# Power_Stages.net
KiCad netlist of a schematic drawn in Altium Designer
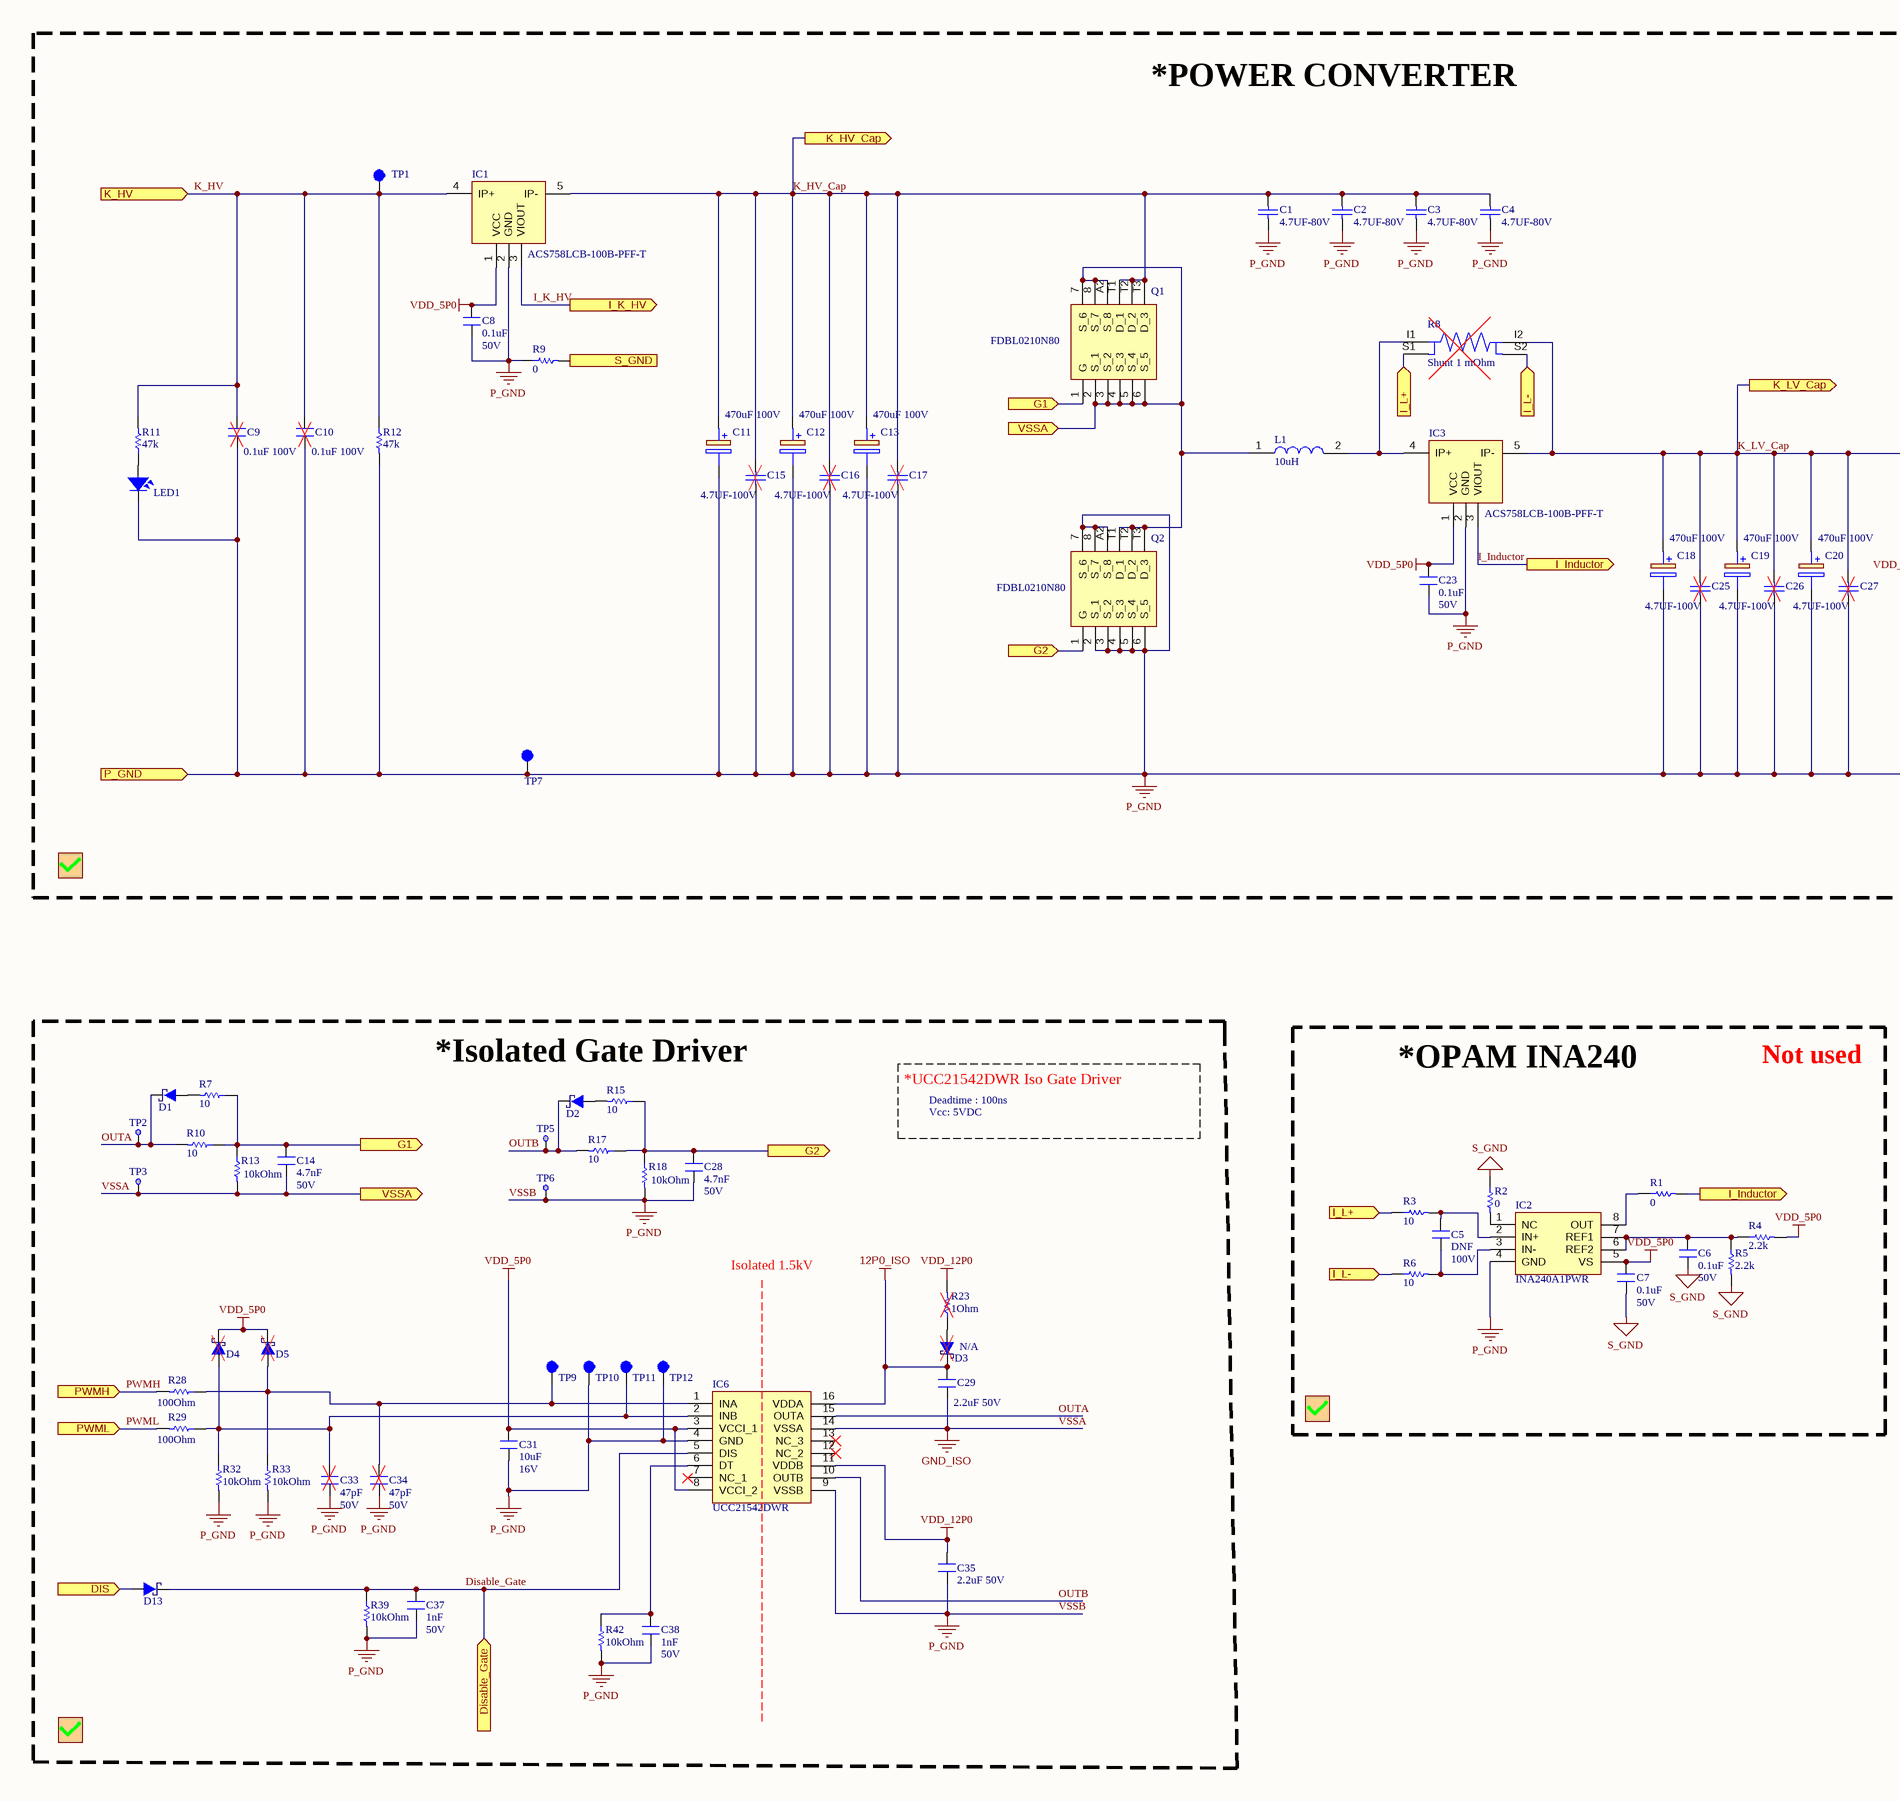
[diagram p0: Power Stages.SchDoc, left]
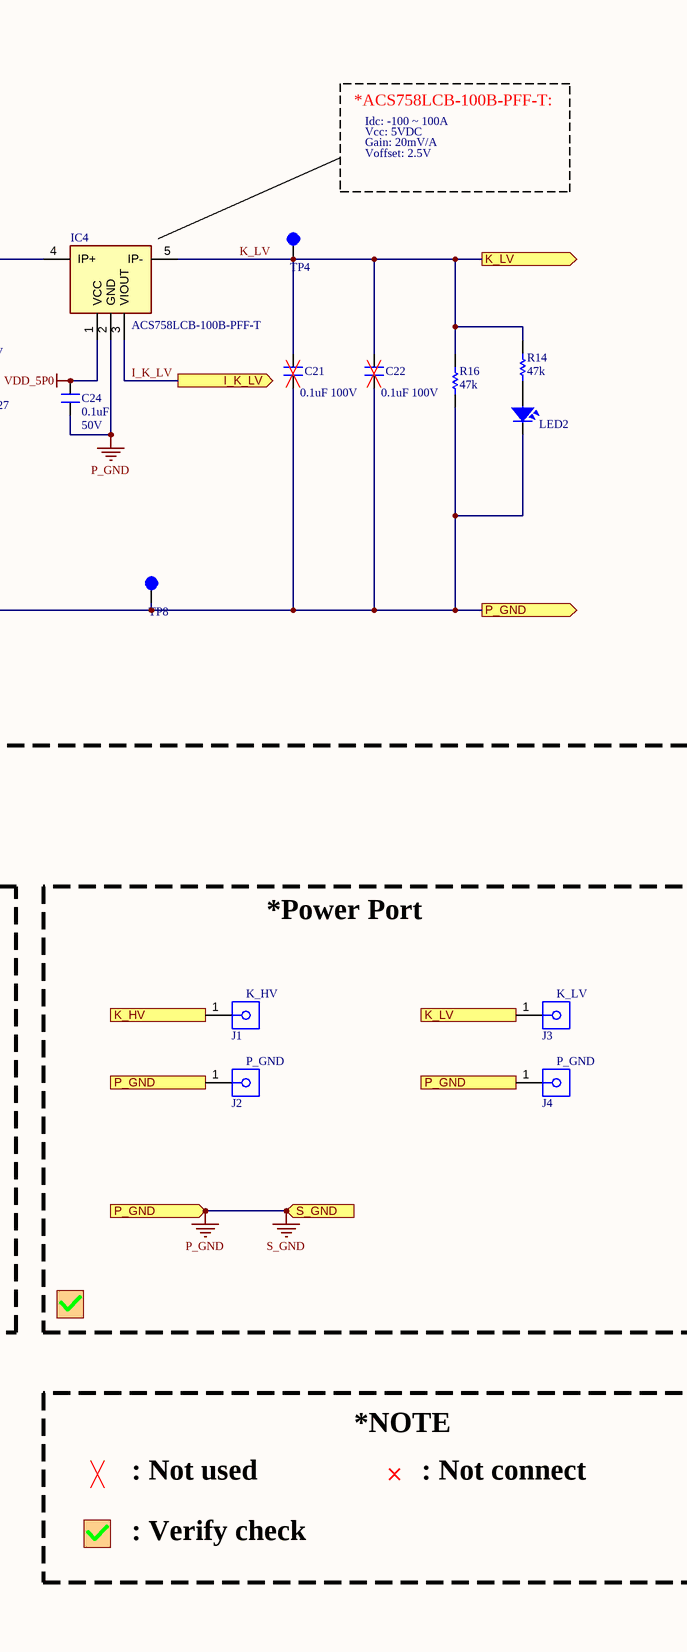
[diagram p1: Power Stages.SchDoc, right]

(export (version "E")
  (design (tool "Eeschema 10.0.6"))
  (components
    (comp (ref "C1")
      (value "4.7UF-80V")
      (footprint "C_1210")
      (description "CAP CER 4.7uF 80V X7R 1210")
      (fields
        (field (name "PART NUMBER") "GRM32ER71K475KE14L")
        (field (name "MANUFACTURER") "TDK Corporation")
      )
      (libsource (lib "DC_DC_Power_V3.0") (part "Cap 1210"))
    )
    (comp (ref "C2")
      (value "4.7UF-80V")
      (footprint "C_1210")
      (description "CAP CER 4.7uF 80V X7R 1210")
      (fields
        (field (name "PART NUMBER") "GRM32ER71K475KE14L")
        (field (name "MANUFACTURER") "TDK Corporation")
      )
      (libsource (lib "DC_DC_Power_V3.0") (part "Cap 1210"))
    )
    (comp (ref "C3")
      (value "4.7UF-80V")
      (footprint "C_1210")
      (description "CAP CER 4.7uF 80V X7R 1210")
      (fields
        (field (name "PART NUMBER") "GRM32ER71K475KE14L")
        (field (name "MANUFACTURER") "TDK Corporation")
      )
      (libsource (lib "DC_DC_Power_V3.0") (part "Cap 1210"))
    )
    (comp (ref "C4")
      (value "4.7UF-80V")
      (footprint "C_1210")
      (description "CAP CER 4.7uF 80V X7R 1210")
      (fields
        (field (name "PART NUMBER") "GRM32ER71K475KE14L")
        (field (name "MANUFACTURER") "TDK Corporation")
      )
      (libsource (lib "DC_DC_Power_V3.0") (part "Cap 1210"))
    )
    (comp (ref "C5")
      (value "DNF")
      (footprint "C_0603")
      (fields
        (field (name "MANUFACTURER") "Murata Electronics")
        (field (name "PART NUMBER") "GCM188R71E102KA37D")
        (field (name "ALTIUM_VALUE") "100V")
      )
      (libsource (lib "S1200_Capacitor") (part "Cap_Cer_0603_1nF"))
    )
    (comp (ref "C6")
      (value "0.1uF")
      (footprint "C_0603")
      (description "CAP CER 0.1UF 50V X7R 0603")
      (fields
        (field (name "MANUFACTURER") "Murata Electronics")
        (field (name "PART NUMBER") "GCM188R71E102KA37D")
        (field (name "ALTIUM_VALUE") "50V")
      )
      (libsource (lib "S1200_Capacitor") (part "Cap_Cer_0603_1nF"))
    )
    (comp (ref "C7")
      (value "0.1uF")
      (footprint "C_0603")
      (description "CAP CER 0.1UF 50V X7R 0603")
      (fields
        (field (name "MANUFACTURER") "Murata Electronics")
        (field (name "PART NUMBER") "GCM188R71E102KA37D")
        (field (name "ALTIUM_VALUE") "50V")
      )
      (libsource (lib "S1200_Capacitor") (part "Cap_Cer_0603_1nF"))
    )
    (comp (ref "C8")
      (value "0.1uF")
      (footprint "C_0603")
      (description "CAP CER 0.1UF 16V X5R 0603")
      (fields
        (field (name "MANUFACTURER") "Murata Electronics")
        (field (name "PART NUMBER") "CL21A106KOCLRNC")
        (field (name "ALTIUM_VALUE") "50V")
      )
      (libsource (lib "S1200_Capacitor") (part "Cap_Cer_0603_1nF_25V"))
    )
    (comp (ref "C9")
      (value "0.1uF 100V")
      (footprint "C_1206")
      (description "Ceramic Capacitor 1206 (+-10% TH)/(+10%SMD)")
      (fields
        (field (name "MANUFACTURER") "TDK Corporation")
        (field (name "PART NUMBER") "C3216X7R2A105K160AA")
      )
      (libsource (lib "S1200_Capacitor") (part "Cap_Cer_1206_1uF"))
    )
    (comp (ref "C10")
      (value "0.1uF 100V")
      (footprint "C_1206")
      (description "Ceramic Capacitor 1206 (+-10% TH)/(+10%SMD)")
      (fields
        (field (name "MANUFACTURER") "TDK Corporation")
        (field (name "PART NUMBER") "C3216X7R2A105K160AA")
      )
      (libsource (lib "S1200_Capacitor") (part "Cap_Cer_1206_1uF"))
    )
    (comp (ref "C11")
      (value "470uF 100V")
      (footprint "CAP-ALU-13MM*30MM")
      (description "CAP ALUM 470UF 20% 80V RADIAL")
      (fields (field (name "PART NUMBER") "EEU-FS1K471L"))
      (libsource (lib "Tienanh") (part "100ZLH470MEFC16X31.5"))
    )
    (comp (ref "C12")
      (value "470uF 100V")
      (footprint "CAP-ALU-13MM*30MM")
      (description "CAP ALUM 470UF 20% 80V RADIAL")
      (fields (field (name "PART NUMBER") "EEU-FS1K471L"))
      (libsource (lib "Tienanh") (part "100ZLH470MEFC16X31.5"))
    )
    (comp (ref "C13")
      (value "470uF 100V")
      (footprint "CAP-ALU-13MM*30MM")
      (description "CAP ALUM 470UF 20% 80V RADIAL")
      (fields (field (name "PART NUMBER") "EEU-FS1K471L"))
      (libsource (lib "Tienanh") (part "100ZLH470MEFC16X31.5"))
    )
    (comp (ref "C14")
      (value "4.7nF")
      (footprint "C_0603")
      (description "CAP CER 0805 4.7NF 50V C0G 5%")
      (fields
        (field (name "MANUFACTURER") "KEMET")
        (field (name "PART NUMBER") "C0805C472J5GECAUTO")
        (field (name "ALTIUM_VALUE") "50V")
      )
      (libsource (lib "S1200_Capacitor") (part "Cap_Cer_0603_1nF_25V"))
    )
    (comp (ref "C15")
      (value "4.7UF-100V")
      (footprint "C_1210")
      (description "CAP CER 4.7uF 80V X7R 1210")
      (fields
        (field (name "PART NUMBER") "GRM32ER71K475KE14L")
        (field (name "MANUFACTURER") "TDK Corporation")
      )
      (libsource (lib "DC_DC_Power_V3.0") (part "Cap 1210"))
    )
    (comp (ref "C16")
      (value "4.7UF-100V")
      (footprint "C_1210")
      (description "CAP CER 4.7uF 80V X7R 1210")
      (fields
        (field (name "PART NUMBER") "GRM32ER71K475KE14L")
        (field (name "MANUFACTURER") "TDK Corporation")
      )
      (libsource (lib "DC_DC_Power_V3.0") (part "Cap 1210"))
    )
    (comp (ref "C17")
      (value "4.7UF-100V")
      (footprint "C_1210")
      (description "CAP CER 4.7uF 80V X7R 1210")
      (fields
        (field (name "PART NUMBER") "GRM32ER71K475KE14L")
        (field (name "MANUFACTURER") "TDK Corporation")
      )
      (libsource (lib "DC_DC_Power_V3.0") (part "Cap 1210"))
    )
    (comp (ref "C18")
      (value "470uF 100V")
      (footprint "CAP-ALU-13MM*30MM")
      (description "CAP ALUM 470UF 20% 80V RADIAL")
      (fields (field (name "PART NUMBER") "EEU-FS1K471L"))
      (libsource (lib "Tienanh") (part "100ZLH470MEFC16X31.5"))
    )
    (comp (ref "C19")
      (value "470uF 100V")
      (footprint "CAP-ALU-13MM*30MM")
      (description "CAP ALUM 470UF 20% 80V RADIAL")
      (fields (field (name "PART NUMBER") "EEU-FS1K471L"))
      (libsource (lib "Tienanh") (part "100ZLH470MEFC16X31.5"))
    )
    (comp (ref "C20")
      (value "470uF 100V")
      (footprint "CAP-ALU-13MM*30MM")
      (description "CAP ALUM 470UF 20% 80V RADIAL")
      (fields (field (name "PART NUMBER") "EEU-FS1K471L"))
      (libsource (lib "Tienanh") (part "100ZLH470MEFC16X31.5"))
    )
    (comp (ref "C21")
      (value "0.1uF 100V")
      (footprint "C_1206")
      (description "Ceramic Capacitor 1206 (+-10% TH)/(+10%SMD)")
      (fields
        (field (name "MANUFACTURER") "TDK Corporation")
        (field (name "PART NUMBER") "C3216X7R2A105K160AA")
      )
      (libsource (lib "S1200_Capacitor") (part "Cap_Cer_1206_1uF"))
    )
    (comp (ref "C22")
      (value "0.1uF 100V")
      (footprint "C_1206")
      (description "Ceramic Capacitor 1206 (+-10% TH)/(+10%SMD)")
      (fields
        (field (name "MANUFACTURER") "TDK Corporation")
        (field (name "PART NUMBER") "C3216X7R2A105K160AA")
      )
      (libsource (lib "S1200_Capacitor") (part "Cap_Cer_1206_1uF"))
    )
    (comp (ref "C23")
      (value "0.1uF")
      (footprint "C_0603")
      (description "CAP CER 0.1UF 16V X5R 0603")
      (fields
        (field (name "MANUFACTURER") "Murata Electronics")
        (field (name "PART NUMBER") "CL21A106KOCLRNC")
        (field (name "ALTIUM_VALUE") "50V")
      )
      (libsource (lib "S1200_Capacitor") (part "Cap_Cer_0603_1nF_25V"))
    )
    (comp (ref "C24")
      (value "0.1uF")
      (footprint "C_0603")
      (description "CAP CER 0.1UF 16V X5R 0603")
      (fields
        (field (name "MANUFACTURER") "Murata Electronics")
        (field (name "PART NUMBER") "CL21A106KOCLRNC")
        (field (name "ALTIUM_VALUE") "50V")
      )
      (libsource (lib "S1200_Capacitor") (part "Cap_Cer_0603_1nF_25V"))
    )
    (comp (ref "C25")
      (value "4.7UF-100V")
      (footprint "C_1210")
      (description "CAP CER 4.7uF 80V X7R 1210")
      (fields
        (field (name "PART NUMBER") "GRM32ER71K475KE14L")
        (field (name "MANUFACTURER") "TDK Corporation")
      )
      (libsource (lib "DC_DC_Power_V3.0") (part "Cap 1210"))
    )
    (comp (ref "C26")
      (value "4.7UF-100V")
      (footprint "C_1210")
      (description "CAP CER 4.7uF 80V X7R 1210")
      (fields
        (field (name "PART NUMBER") "GRM32ER71K475KE14L")
        (field (name "MANUFACTURER") "TDK Corporation")
      )
      (libsource (lib "DC_DC_Power_V3.0") (part "Cap 1210"))
    )
    (comp (ref "C27")
      (value "4.7UF-100V")
      (footprint "C_1210")
      (description "CAP CER 4.7uF 80V X7R 1210")
      (fields
        (field (name "PART NUMBER") "GRM32ER71K475KE14L")
        (field (name "MANUFACTURER") "TDK Corporation")
      )
      (libsource (lib "DC_DC_Power_V3.0") (part "Cap 1210"))
    )
    (comp (ref "C28")
      (value "4.7nF")
      (footprint "C_0603")
      (description "CAP CER 0805 4.7NF 50V C0G 5%")
      (fields
        (field (name "MANUFACTURER") "KEMET")
        (field (name "PART NUMBER") "C0805C472J5GECAUTO")
        (field (name "ALTIUM_VALUE") "50V")
      )
      (libsource (lib "S1200_Capacitor") (part "Cap_Cer_0603_1nF_25V"))
    )
    (comp (ref "C29")
      (value "2.2uF 50V")
      (footprint "C_1206")
      (description "Ceramic Capacitor 1206 (+-10% TH)/(+10%SMD)")
      (fields
        (field (name "MANUFACTURER") "TDK Corporation")
        (field (name "PART NUMBER") "C3216X7R2A105K160AA")
      )
      (libsource (lib "S1200_Capacitor") (part "Cap_Cer_1206_1uF"))
    )
    (comp (ref "C31")
      (value "10uF")
      (footprint "C_0805")
      (description "CAP CER 10uF 16V X7R 0805")
      (fields
        (field (name "MANUFACTURER") "Kemet")
        (field (name "PART NUMBER") "CL21A106KOCLRNC")
        (field (name "ALTIUM_VALUE") "16V")
      )
      (libsource (lib "S1200_Capacitor") (part "Cap_Cer_0805_10pF"))
    )
    (comp (ref "C33")
      (value "47pF")
      (footprint "C_0603")
      (description "CAP CER 1nF 50V X7R 0603")
      (fields
        (field (name "MANUFACTURER") "Murata Electronics")
        (field (name "PART NUMBER") "GCM188R71E102KA37D")
        (field (name "ALTIUM_VALUE") "50V")
      )
      (libsource (lib "S1200_Capacitor") (part "Cap_Cer_0603_1nF_25V"))
    )
    (comp (ref "C34")
      (value "47pF")
      (footprint "C_0603")
      (description "CAP CER 1nF 50V X7R 0603")
      (fields
        (field (name "MANUFACTURER") "Murata Electronics")
        (field (name "PART NUMBER") "GCM188R71E102KA37D")
        (field (name "ALTIUM_VALUE") "50V")
      )
      (libsource (lib "S1200_Capacitor") (part "Cap_Cer_0603_1nF_25V"))
    )
    (comp (ref "C35")
      (value "2.2uF 50V")
      (footprint "C_1206")
      (description "Ceramic Capacitor 1206 (+-10% TH)/(+10%SMD)")
      (fields
        (field (name "MANUFACTURER") "TDK Corporation")
        (field (name "PART NUMBER") "C3216X7R2A105K160AA")
      )
      (libsource (lib "S1200_Capacitor") (part "Cap_Cer_1206_1uF"))
    )
    (comp (ref "C37")
      (value "1nF")
      (footprint "C_0603")
      (description "CAP CER 1nF 50V X7R 0603")
      (fields
        (field (name "MANUFACTURER") "Murata Electronics")
        (field (name "PART NUMBER") "GCM188R71E102KA37D")
        (field (name "ALTIUM_VALUE") "50V")
      )
      (libsource (lib "S1200_Capacitor") (part "Cap_Cer_0603_1nF_25V"))
    )
    (comp (ref "C38")
      (value "1nF")
      (footprint "C_0603")
      (description "CAP CER 1nF 50V X7R 0603")
      (fields
        (field (name "MANUFACTURER") "Murata Electronics")
        (field (name "PART NUMBER") "GCM188R71E102KA37D")
        (field (name "ALTIUM_VALUE") "50V")
      )
      (libsource (lib "S1200_Capacitor") (part "Cap_Cer_0603_1nF_25V"))
    )
    (comp (ref "D1")
      (value "B0520WS-7-F")
      (footprint "SOD323F")
      (description "DIODE SCHOTTKY 20V 1A SOD323F")
      (fields
        (field (name "MANUFACTURER") "Nexperia USA Inc.")
        (field (name "PART NUMBER") "PMEG2010AEJ,115")
      )
      (libsource (lib "Motor Control SELEX MOTORS JSC") (part "PMEG2010AEJ,115"))
    )
    (comp (ref "D2")
      (value "B0520WS-7-F")
      (footprint "SOD323F")
      (description "DIODE SCHOTTKY 20V 1A SOD323F")
      (fields
        (field (name "MANUFACTURER") "Nexperia USA Inc.")
        (field (name "PART NUMBER") "PMEG2010AEJ,115")
      )
      (libsource (lib "Motor Control SELEX MOTORS JSC") (part "PMEG2010AEJ,115"))
    )
    (comp (ref "D3")
      (value "PMEG2010AEJ,115")
      (footprint "SOD123")
      (description "DIODE SCHOTTKY 20V 1A SOD323F")
      (fields (field (name "MANUFACTURER") "Nexperia USA Inc.") (field (name "VOLTAGE") "20 V"))
      (libsource (lib "Motor Control SELEX MOTORS JSC") (part "PMEG2010AEJ,115"))
    )
    (comp (ref "D4")
      (value "PMEG2010AEJ,115")
      (footprint "SOD323F")
      (description "DIODE SCHOTTKY 30V 0.2A SOD323F")
      (fields (field (name "MANUFACTURER") "Nexperia USA Inc.") (field (name "PART NUMBER") "BAT54HT1G"))
      (libsource (lib "Motor Control SELEX MOTORS JSC") (part "PMEG2010AEJ,115"))
    )
    (comp (ref "D5")
      (value "PMEG2010AEJ,115")
      (footprint "SOD323F")
      (description "DIODE SCHOTTKY 30V 0.2A SOD323F")
      (fields (field (name "MANUFACTURER") "Nexperia USA Inc.") (field (name "PART NUMBER") "BAT54HT1G"))
      (libsource (lib "Motor Control SELEX MOTORS JSC") (part "PMEG2010AEJ,115"))
    )
    (comp (ref "D13")
      (value "PMEG2010AEJ,115")
      (footprint "SOD323F")
      (description "DIODE SCHOTTKY 20V 1A SOD323F")
      (fields (field (name "MANUFACTURER") "Nexperia USA Inc.") (field (name "VOLTAGE") "20 V"))
      (libsource (lib "Motor Control SELEX MOTORS JSC") (part "PMEG2010AEJ,115"))
    )
    (comp (ref "IC1")
      (value "ACS758LCB-100B-PFF-T")
      (footprint "ACS772ECB200BPFFT")
      (description "Integrated Circuit")
      (fields (field (name "MOUSER PART NUMBER") "250-758LCB100BPFFT"))
      (libsource (lib "Tienanh") (part "ACS758LCB-100B-PFF-T"))
    )
    (comp (ref "IC2")
      (value "INA240A1PWR")
      (footprint "SOP65P640X120-8N")
      (description "Integrated Circuit")
      (fields (field (name "MOUSER PART NUMBER") "595-INA240A1PWR"))
      (libsource (lib "*") (part "INA240A1PWR"))
    )
    (comp (ref "IC3")
      (value "ACS758LCB-100B-PFF-T")
      (footprint "ACS772ECB200BPFFT")
      (description "Integrated Circuit")
      (fields (field (name "MOUSER PART NUMBER") "250-758LCB100BPFFT"))
      (libsource (lib "Tienanh") (part "ACS758LCB-100B-PFF-T"))
    )
    (comp (ref "IC4")
      (value "ACS758LCB-100B-PFF-T")
      (footprint "ACS772ECB200BPFFT")
      (description "Integrated Circuit")
      (fields (field (name "MOUSER PART NUMBER") "250-758LCB100BPFFT"))
      (libsource (lib "Tienanh") (part "ACS758LCB-100B-PFF-T"))
    )
    (comp (ref "IC6")
      (value "UCC21542DWR")
      (footprint "SamacSys:SOIC127P1030X265-16N")
      (description "REINFORCED ISOLATION DUAL-CHANNE")
      (fields (field (name "MOUSER PART NUMBER") "595-UCC21542DWR"))
      (libsource (lib "*") (part "UCC21542DWR"))
    )
    (comp (ref "J1")
      (value "K_HV")
      (footprint "HOLE_5mm_RED")
      (description "Electric Pole 1")
      (libsource (lib "Motor Control SELEX MOTORS JSC") (part "CONN_1P"))
    )
    (comp (ref "J2")
      (value "P_GND")
      (footprint "HOLE_5mm_BLACK")
      (description "Electric Pole 1")
      (libsource (lib "Motor Control SELEX MOTORS JSC") (part "CONN_1P"))
    )
    (comp (ref "J3")
      (value "K_LV")
      (footprint "HOLE_5mm_RED")
      (description "Electric Pole 1")
      (libsource (lib "Motor Control SELEX MOTORS JSC") (part "CONN_1P"))
    )
    (comp (ref "J4")
      (value "P_GND")
      (footprint "HOLE_5mm_BLACK")
      (description "Electric Pole 1")
      (libsource (lib "Motor Control SELEX MOTORS JSC") (part "CONN_1P"))
    )
    (comp (ref "L1")
      (value "10uH")
      (footprint "CSCF3218-6R8MC")
      (description "10-µH with a specified saturation current of 70-A DC")
      (libsource (lib "Sync_Buck1") (part "IHDF1300AEEH4R7K10"))
    )
    (comp (ref "LED1")
      (value "LED SMD")
      (footprint "SM-LED-0805-Blue")
      (description "LED BLUE 1/4W 0805")
      (libsource (lib "syhaunguyen") (part "LED-SMD-0805"))
    )
    (comp (ref "LED2")
      (value "LED SMD")
      (footprint "SM-LED-0805-Blue")
      (description "LED BLUE 1/4W 0805")
      (libsource (lib "syhaunguyen") (part "LED-SMD-0805"))
    )
    (comp (ref "Q1")
      (value "FDBL0210N80")
      (footprint "NTBLS1D5N10MC - duplicate")
      (description "MOSFET N-CH 80V 240A 8HPSOF")
      (fields (field (name "ARROW PART NUMBER") "IPLU300N04S4R8XTMA1"))
      (libsource (lib "*") (part "IPLU300N04S4R8XTMA1"))
    )
    (comp (ref "Q2")
      (value "FDBL0210N80")
      (footprint "NTBLS1D5N10MC - duplicate")
      (description "MOSFET N-CH 80V 240A 8HPSOF")
      (fields (field (name "ARROW PART NUMBER") "IPLU300N04S4R8XTMA1"))
      (libsource (lib "*") (part "IPLU300N04S4R8XTMA1"))
    )
    (comp (ref "R1")
      (value "0")
      (footprint "R_0603")
      (description "RES 0 OHM 1% 1/8W 0603")
      (fields
        (field (name "MANUFACTURER") "KOA Speer Electronics, Inc.")
        (field (name "PART NUMBER") "RK73H1JRTTD10R0F")
      )
      (libsource (lib "S1100_Resistor_FerriteBead") (part "Resistor_0603_10Ohm 1%"))
    )
    (comp (ref "R2")
      (value "0")
      (footprint "R_0603")
      (description "RES 0 OHM 1% 1/8W 0603")
      (fields
        (field (name "MANUFACTURER") "KOA Speer Electronics, Inc.")
        (field (name "PART NUMBER") "RK73H1JRTTD10R0F")
      )
      (libsource (lib "S1100_Resistor_FerriteBead") (part "Resistor_0603_10Ohm 1%"))
    )
    (comp (ref "R3")
      (value "10")
      (footprint "R_0603")
      (description "RES 10 OHM 1% 1/8W 0603")
      (fields
        (field (name "MANUFACTURER") "KOA Speer Electronics, Inc.")
        (field (name "PART NUMBER") "RK73H1JRTTD10R0F")
      )
      (libsource (lib "S1100_Resistor_FerriteBead") (part "Resistor_0603_10Ohm 1%"))
    )
    (comp (ref "R4")
      (value "2.2k")
      (footprint "R_0603")
      (description "RES 2.2k OHM 1% 1/8W 0603")
      (fields
        (field (name "MANUFACTURER") "KOA Speer Electronics, Inc.")
        (field (name "PART NUMBER") "RK73H1JRTTD10R0F")
      )
      (libsource (lib "S1100_Resistor_FerriteBead") (part "Resistor_0603_10Ohm 1%"))
    )
    (comp (ref "R5")
      (value "2.2k")
      (footprint "R_0603")
      (description "RES 2.2k OHM 1% 1/8W 0603")
      (fields
        (field (name "MANUFACTURER") "KOA Speer Electronics, Inc.")
        (field (name "PART NUMBER") "RK73H1JRTTD10R0F")
      )
      (libsource (lib "S1100_Resistor_FerriteBead") (part "Resistor_0603_10Ohm 1%"))
    )
    (comp (ref "R6")
      (value "10")
      (footprint "R_0603")
      (description "RES 10 OHM 1% 1/8W 0603")
      (fields
        (field (name "MANUFACTURER") "KOA Speer Electronics, Inc.")
        (field (name "PART NUMBER") "RK73H1JRTTD10R0F")
      )
      (libsource (lib "S1100_Resistor_FerriteBead") (part "Resistor_0603_10Ohm 1%"))
    )
    (comp (ref "R7")
      (value "10")
      (footprint "R_0805")
      (description "RES 10 OHM 1% 1/8W 0805")
      (fields (field (name "PART NUMBER") "RE0805FRE0710RL") (field (name "MANUFACTURER") "YAGEO"))
      (libsource (lib "S1100_Resistor_FerriteBead") (part "Resistor_0805_10Ohm"))
    )
    (comp (ref "R8")
      (value "Shunt 1 mOhm")
      (footprint "PSG4/PSF4")
      (description "RES 1m OHM 1% 10W NONSTANDARD")
      (fields
        (field (name "MANUFACTURER") "KOA Speer Electronics, Inc.")
        (field (name "PART NUMBER") "PSG4NTEBL500F")
      )
      (libsource (lib "Motor Control SELEX MOTORS JSC") (part "PSG4NTEBL500F"))
    )
    (comp (ref "R9")
      (value "0")
      (footprint "R_0603")
      (description "RES 0 OHM 1% 1/10W 0603")
      (fields (field (name "MANUFACTURER") "YAGEO") (field (name "PART NUMBER") "RC0603FR-7W10KL"))
      (libsource (lib "S1100_Resistor_FerriteBead") (part "Resistor_0603_10kOhm 1%"))
    )
    (comp (ref "R10")
      (value "10")
      (footprint "R_0805")
      (description "RES 10 OHM 1% 1/8W 0805")
      (fields (field (name "PART NUMBER") "RE0805FRE0710RL") (field (name "MANUFACTURER") "YAGEO"))
      (libsource (lib "S1100_Resistor_FerriteBead") (part "Resistor_0805_10Ohm"))
    )
    (comp (ref "R11")
      (value "47k")
      (footprint "R_0603")
      (description "RES 47K OHM 1% 1/10W 0603")
      (fields (field (name "MANUFACTURER") "YAGEO") (field (name "PART NUMBER") "RC0603FR-07100KL"))
      (libsource (lib "S1100_Resistor_FerriteBead") (part "Resistor_0603_10Ohm 1%"))
    )
    (comp (ref "R12")
      (value "47k")
      (footprint "R_1206")
      (description "RES 47K OHM 1/4W 1206")
      (fields (field (name "MANUFACTURER") "YAGEO") (field (name "PART NUMBER") "RC1206JR-070RL"))
      (libsource (lib "S1100_Resistor_FerriteBead") (part "Resistor_1206_0Ohm"))
    )
    (comp (ref "R13")
      (value "10kOhm")
      (footprint "R_0603")
      (description "RES 10K OHM 1% 1/10W 0603")
      (fields (field (name "MANUFACTURER") "YAGEO") (field (name "PART NUMBER") "RC0603FR-7W10KL"))
      (libsource (lib "S1100_Resistor_FerriteBead") (part "Resistor_0603_10kOhm 1%"))
    )
    (comp (ref "R14")
      (value "47k")
      (footprint "R_0603")
      (description "RES 47K OHM 1% 1/10W 0603")
      (fields (field (name "MANUFACTURER") "YAGEO") (field (name "PART NUMBER") "RC0603FR-07100KL"))
      (libsource (lib "S1100_Resistor_FerriteBead") (part "Resistor_0603_10Ohm 1%"))
    )
    (comp (ref "R15")
      (value "10")
      (footprint "R_0805")
      (description "RES 10 OHM 1% 1/8W 0805")
      (fields (field (name "PART NUMBER") "RE0805FRE0710RL") (field (name "MANUFACTURER") "YAGEO"))
      (libsource (lib "S1100_Resistor_FerriteBead") (part "Resistor_0805_10Ohm"))
    )
    (comp (ref "R16")
      (value "47k")
      (footprint "R_1206")
      (description "RES 47K OHM 1/4W 1206")
      (fields (field (name "MANUFACTURER") "YAGEO") (field (name "PART NUMBER") "RC1206JR-070RL"))
      (libsource (lib "S1100_Resistor_FerriteBead") (part "Resistor_1206_0Ohm"))
    )
    (comp (ref "R17")
      (value "10")
      (footprint "R_0805")
      (description "RES 10 OHM 1% 1/8W 0805")
      (fields (field (name "PART NUMBER") "RE0805FRE0710RL") (field (name "MANUFACTURER") "YAGEO"))
      (libsource (lib "S1100_Resistor_FerriteBead") (part "Resistor_0805_10Ohm"))
    )
    (comp (ref "R18")
      (value "10kOhm")
      (footprint "R_0603")
      (description "RES 10K OHM 1% 1/10W 0603")
      (fields (field (name "MANUFACTURER") "YAGEO") (field (name "PART NUMBER") "RC0603FR-7W10KL"))
      (libsource (lib "S1100_Resistor_FerriteBead") (part "Resistor_0603_10kOhm 1%"))
    )
    (comp (ref "R23")
      (value "1Ohm")
      (footprint "R_0603")
      (description "RES 1OHM 1% 1/8W 0603")
      (fields (field (name "MANUFACTURER") "Vishay Dale") (field (name "PART NUMBER") "MCT06030C1008FP500"))
      (libsource (lib "S1100_Resistor_FerriteBead") (part "Resistor_0603_1Ohm"))
    )
    (comp (ref "R28")
      (value "100Ohm")
      (footprint "R_0603")
      (description "RES 100 OHM 1% 1/8W 0603")
      (fields
        (field (name "MANUFACTURER") "KOA Speer Electronics, Inc.")
        (field (name "PART NUMBER") "RK73H1JRTTD1000F")
      )
      (libsource (lib "S1100_Resistor_FerriteBead") (part "Resistor_0603_100Ohm"))
    )
    (comp (ref "R29")
      (value "100Ohm")
      (footprint "R_0603")
      (description "RES 100 OHM 1% 1/8W 0603")
      (fields
        (field (name "MANUFACTURER") "KOA Speer Electronics, Inc.")
        (field (name "PART NUMBER") "RK73H1JRTTD1000F")
      )
      (libsource (lib "S1100_Resistor_FerriteBead") (part "Resistor_0603_100Ohm"))
    )
    (comp (ref "R32")
      (value "10kOhm")
      (footprint "R_0603")
      (description "RES 10 kOHM 1% 1/8W 0603")
      (fields
        (field (name "MANUFACTURER") "KOA Speer Electronics, Inc.")
        (field (name "PART NUMBER") "RK73H1JRTTD1000F")
      )
      (libsource (lib "S1100_Resistor_FerriteBead") (part "Resistor_0603_100Ohm"))
    )
    (comp (ref "R33")
      (value "10kOhm")
      (footprint "R_0603")
      (description "RES 10 kOHM 1% 1/8W 0603")
      (fields
        (field (name "MANUFACTURER") "KOA Speer Electronics, Inc.")
        (field (name "PART NUMBER") "RK73H1JRTTD1000F")
      )
      (libsource (lib "S1100_Resistor_FerriteBead") (part "Resistor_0603_100Ohm"))
    )
    (comp (ref "R39")
      (value "10kOhm")
      (footprint "R_0603")
      (description "RES 10 kOHM 1% 1/8W 0603")
      (fields
        (field (name "MANUFACTURER") "KOA Speer Electronics, Inc.")
        (field (name "PART NUMBER") "RK73H1JRTTD1000F")
      )
      (libsource (lib "S1100_Resistor_FerriteBead") (part "Resistor_0603_100Ohm"))
    )
    (comp (ref "R42")
      (value "10kOhm")
      (footprint "R_0603")
      (description "RES 10 kOHM 1% 1/8W 0603")
      (fields
        (field (name "MANUFACTURER") "KOA Speer Electronics, Inc.")
        (field (name "PART NUMBER") "RK73H1JRTTD1000F")
      )
      (libsource (lib "S1100_Resistor_FerriteBead") (part "Resistor_0603_100Ohm"))
    )
    (comp (ref "TP1")
      (value "Test Point")
      (footprint "TP_1mm_through_hole")
      (description "PC TEST POINT COMPACT RED")
      (fields (field (name "PART NUMBER") "5005") (field (name "MANUFACTURER") "Keystone Electronics"))
      (libsource (lib "Tienanh") (part "Test Point"))
    )
    (comp (ref "TP2")
      (value "TP")
      (footprint "TP_1mm")
      (description "Test Point")
      (fields (field (name "CREATOR") "SELEX MOTORS JSC"))
      (libsource (lib "S1400_Test_Point") (part "Test_Point_1mm"))
    )
    (comp (ref "TP3")
      (value "TP")
      (footprint "TP_1mm")
      (description "Test Point")
      (fields (field (name "CREATOR") "SELEX MOTORS JSC"))
      (libsource (lib "S1400_Test_Point") (part "Test_Point_1mm"))
    )
    (comp (ref "TP4")
      (value "Test Point")
      (footprint "TP_1mm_through_hole")
      (description "PC TEST POINT COMPACT RED")
      (fields (field (name "PART NUMBER") "5005") (field (name "MANUFACTURER") "Keystone Electronics"))
      (libsource (lib "Tienanh") (part "Test Point"))
    )
    (comp (ref "TP5")
      (value "TP")
      (footprint "TP_1mm")
      (description "Test Point")
      (fields (field (name "CREATOR") "SELEX MOTORS JSC"))
      (libsource (lib "S1400_Test_Point") (part "Test_Point_1mm"))
    )
    (comp (ref "TP6")
      (value "TP")
      (footprint "TP_1mm")
      (description "Test Point")
      (fields (field (name "CREATOR") "SELEX MOTORS JSC"))
      (libsource (lib "S1400_Test_Point") (part "Test_Point_1mm"))
    )
    (comp (ref "TP7")
      (value "Test Point")
      (footprint "TP_1mm_through_hole")
      (description "PC TEST POINT COMPACT RED")
      (fields (field (name "PART NUMBER") "5005") (field (name "MANUFACTURER") "Keystone Electronics"))
      (libsource (lib "Tienanh") (part "Test Point"))
    )
    (comp (ref "TP8")
      (value "Test Point")
      (footprint "TP_1mm_through_hole")
      (description "PC TEST POINT COMPACT RED")
      (fields (field (name "PART NUMBER") "5005") (field (name "MANUFACTURER") "Keystone Electronics"))
      (libsource (lib "Tienanh") (part "Test Point"))
    )
    (comp (ref "TP9")
      (value "Test Point")
      (footprint "TP_1mm_through_hole")
      (description "PC TEST POINT COMPACT RED")
      (fields (field (name "PART NUMBER") "5005") (field (name "MANUFACTURER") "Keystone Electronics"))
      (libsource (lib "Tienanh") (part "Test Point"))
    )
    (comp (ref "TP10")
      (value "Test Point")
      (footprint "TP_1mm_through_hole")
      (description "PC TEST POINT COMPACT RED")
      (fields (field (name "PART NUMBER") "5005") (field (name "MANUFACTURER") "Keystone Electronics"))
      (libsource (lib "Tienanh") (part "Test Point"))
    )
    (comp (ref "TP11")
      (value "Test Point")
      (footprint "TP_1mm_through_hole")
      (description "PC TEST POINT COMPACT RED")
      (fields (field (name "PART NUMBER") "5005") (field (name "MANUFACTURER") "Keystone Electronics"))
      (libsource (lib "Tienanh") (part "Test Point"))
    )
    (comp (ref "TP12")
      (value "Test Point")
      (footprint "TP_1mm_through_hole")
      (description "PC TEST POINT COMPACT RED")
      (fields (field (name "PART NUMBER") "5005") (field (name "MANUFACTURER") "Keystone Electronics"))
      (libsource (lib "Tienanh") (part "Test Point"))
    )
  )
  (nets
    (net (code "1") (name "/DIS") (class "Default")
      (node (ref "D13") (pin "1") (pinfunction "1_1") (pintype "passive"))
    )
    (net (code "2") (name "/Disable_Gate") (class "Default")
      (node (ref "C37") (pin "2") (pinfunction "2_2") (pintype "passive"))
      (node (ref "D13") (pin "2") (pinfunction "2_2") (pintype "passive"))
      (node (ref "IC6") (pin "5") (pinfunction "DIS_5") (pintype "passive"))
      (node (ref "R39") (pin "2") (pinfunction "2_2") (pintype "passive"))
    )
    (net (code "3") (name "/G1") (class "Default")
      (node (ref "C14") (pin "2") (pinfunction "2_2") (pintype "passive"))
      (node (ref "Q1") (pin "1") (pinfunction "G_1") (pintype "passive"))
      (node (ref "R10") (pin "2") (pinfunction "2_2") (pintype "passive"))
      (node (ref "R13") (pin "2") (pinfunction "2_2") (pintype "passive"))
      (node (ref "R7") (pin "2") (pinfunction "2_2") (pintype "passive"))
    )
    (net (code "4") (name "/G2") (class "Default")
      (node (ref "C28") (pin "2") (pinfunction "2_2") (pintype "passive"))
      (node (ref "Q2") (pin "1") (pinfunction "G_1") (pintype "passive"))
      (node (ref "R15") (pin "2") (pinfunction "2_2") (pintype "passive"))
      (node (ref "R17") (pin "2") (pinfunction "2_2") (pintype "passive"))
      (node (ref "R18") (pin "2") (pinfunction "2_2") (pintype "passive"))
    )
    (net (code "5") (name "/I_Inductor") (class "Default")
      (node (ref "IC3") (pin "3") (pinfunction "VIOUT_3") (pintype "passive"))
      (node (ref "R1") (pin "1") (pinfunction "1_1") (pintype "passive"))
    )
    (net (code "6") (name "/I_K_HV") (class "Default")
      (node (ref "IC1") (pin "3") (pinfunction "VIOUT_3") (pintype "passive"))
    )
    (net (code "7") (name "/I_K_LV") (class "Default")
      (node (ref "IC4") (pin "3") (pinfunction "VIOUT_3") (pintype "passive"))
    )
    (net (code "8") (name "/I_L+") (class "Default")
      (node (ref "R3") (pin "2") (pinfunction "2_2") (pintype "passive"))
      (node (ref "R8") (pin "S1") (pinfunction "S1_S1") (pintype "passive"))
    )
    (net (code "9") (name "/I_L-") (class "Default")
      (node (ref "R6") (pin "2") (pinfunction "2_2") (pintype "passive"))
      (node (ref "R8") (pin "S2") (pinfunction "S2_S2") (pintype "passive"))
    )
    (net (code "10") (name "/K_HV") (class "Default")
      (node (ref "C10") (pin "2") (pinfunction "2_2") (pintype "passive"))
      (node (ref "C9") (pin "2") (pinfunction "2_2") (pintype "passive"))
      (node (ref "IC1") (pin "4") (pinfunction "IP+_4") (pintype "passive"))
      (node (ref "J1") (pin "1") (pinfunction "1_1") (pintype "passive"))
      (node (ref "R11") (pin "1") (pinfunction "1_1") (pintype "passive"))
      (node (ref "R12") (pin "2") (pinfunction "2_2") (pintype "passive"))
      (node (ref "TP1") (pin "1") (pinfunction "B_1") (pintype "passive"))
    )
    (net (code "11") (name "/K_HV_Cap") (class "Default")
      (node (ref "C1") (pin "2") (pinfunction "2_2") (pintype "passive"))
      (node (ref "C11") (pin "1") (pinfunction "+_1") (pintype "passive"))
      (node (ref "C12") (pin "1") (pinfunction "+_1") (pintype "passive"))
      (node (ref "C13") (pin "1") (pinfunction "+_1") (pintype "passive"))
      (node (ref "C15") (pin "2") (pinfunction "2_2") (pintype "passive"))
      (node (ref "C16") (pin "2") (pinfunction "2_2") (pintype "passive"))
      (node (ref "C17") (pin "2") (pinfunction "2_2") (pintype "passive"))
      (node (ref "C2") (pin "2") (pinfunction "2_2") (pintype "passive"))
      (node (ref "C3") (pin "2") (pinfunction "2_2") (pintype "passive"))
      (node (ref "C4") (pin "2") (pinfunction "2_2") (pintype "passive"))
      (node (ref "IC1") (pin "5") (pinfunction "IP-_5") (pintype "passive"))
      (node (ref "Q1") (pin "T1") (pinfunction "D_1_T1") (pintype "passive"))
      (node (ref "Q1") (pin "T2") (pinfunction "D_2_T2") (pintype "passive"))
      (node (ref "Q1") (pin "T3") (pinfunction "D_3_T3") (pintype "passive"))
    )
    (net (code "12") (name "/K_LV") (class "Default")
      (node (ref "C21") (pin "2") (pinfunction "2_2") (pintype "passive"))
      (node (ref "C22") (pin "2") (pinfunction "2_2") (pintype "passive"))
      (node (ref "IC4") (pin "5") (pinfunction "IP-_5") (pintype "passive"))
      (node (ref "J3") (pin "1") (pinfunction "1_1") (pintype "passive"))
      (node (ref "R14") (pin "1") (pinfunction "1_1") (pintype "passive"))
      (node (ref "R16") (pin "2") (pinfunction "2_2") (pintype "passive"))
      (node (ref "TP4") (pin "1") (pinfunction "B_1") (pintype "passive"))
    )
    (net (code "13") (name "/K_LV_Cap") (class "Default")
      (node (ref "C18") (pin "1") (pinfunction "+_1") (pintype "passive"))
      (node (ref "C19") (pin "1") (pinfunction "+_1") (pintype "passive"))
      (node (ref "C20") (pin "1") (pinfunction "+_1") (pintype "passive"))
      (node (ref "C25") (pin "2") (pinfunction "2_2") (pintype "passive"))
      (node (ref "C26") (pin "2") (pinfunction "2_2") (pintype "passive"))
      (node (ref "C27") (pin "2") (pinfunction "2_2") (pintype "passive"))
      (node (ref "IC3") (pin "5") (pinfunction "IP-_5") (pintype "passive"))
      (node (ref "IC4") (pin "4") (pinfunction "IP+_4") (pintype "passive"))
      (node (ref "R8") (pin "I2") (pinfunction "I2_I2") (pintype "passive"))
    )
    (net (code "14") (name "/OUTA") (class "Default")
      (node (ref "D1") (pin "2") (pinfunction "2_2") (pintype "passive"))
      (node (ref "IC6") (pin "15") (pinfunction "OUTA_15") (pintype "passive"))
      (node (ref "R10") (pin "1") (pinfunction "1_1") (pintype "passive"))
      (node (ref "TP2") (pin "1") (pinfunction "TP_1") (pintype "passive"))
    )
    (net (code "15") (name "/OUTB") (class "Default")
      (node (ref "D2") (pin "2") (pinfunction "2_2") (pintype "passive"))
      (node (ref "IC6") (pin "10") (pinfunction "OUTB_10") (pintype "passive"))
      (node (ref "R17") (pin "1") (pinfunction "1_1") (pintype "passive"))
      (node (ref "TP5") (pin "1") (pinfunction "TP_1") (pintype "passive"))
    )
    (net (code "16") (name "/PWMH") (class "Default")
      (node (ref "R28") (pin "1") (pinfunction "1_1") (pintype "passive"))
    )
    (net (code "17") (name "/PWML") (class "Default")
      (node (ref "R29") (pin "1") (pinfunction "1_1") (pintype "passive"))
    )
    (net (code "18") (name "12P0_ISO") (class "Default")
      (node (ref "C29") (pin "2") (pinfunction "2_2") (pintype "passive"))
      (node (ref "D3") (pin "2") (pinfunction "2_2") (pintype "passive"))
      (node (ref "IC6") (pin "16") (pinfunction "VDDA_16") (pintype "passive"))
    )
    (net (code "19") (name "GND_ISO") (class "Default")
      (node (ref "C14") (pin "1") (pinfunction "1_1") (pintype "passive"))
      (node (ref "C29") (pin "1") (pinfunction "1_1") (pintype "passive"))
      (node (ref "IC6") (pin "14") (pinfunction "VSSA_14") (pintype "passive"))
      (node (ref "L1") (pin "1") (pinfunction "1_1") (pintype "passive"))
      (node (ref "Q1") (pin "2") (pinfunction "S_1_2") (pintype "passive"))
      (node (ref "Q1") (pin "3") (pinfunction "S_2_3") (pintype "passive"))
      (node (ref "Q1") (pin "4") (pinfunction "S_3_4") (pintype "passive"))
      (node (ref "Q1") (pin "5") (pinfunction "S_4_5") (pintype "passive"))
      (node (ref "Q1") (pin "6") (pinfunction "S_5_6") (pintype "passive"))
      (node (ref "Q1") (pin "7") (pinfunction "S_6_7") (pintype "passive"))
      (node (ref "Q1") (pin "8") (pinfunction "S_7_8") (pintype "passive"))
      (node (ref "Q1") (pin "A2") (pinfunction "S_8_A2") (pintype "passive"))
      (node (ref "Q2") (pin "T1") (pinfunction "D_1_T1") (pintype "passive"))
      (node (ref "Q2") (pin "T2") (pinfunction "D_2_T2") (pintype "passive"))
      (node (ref "Q2") (pin "T3") (pinfunction "D_3_T3") (pintype "passive"))
      (node (ref "R13") (pin "1") (pinfunction "1_1") (pintype "passive"))
      (node (ref "TP3") (pin "1") (pinfunction "TP_1") (pintype "passive"))
    )
    (net (code "20") (name "Net-(D1-Pad1)") (class "Default")
      (node (ref "D1") (pin "1") (pinfunction "1_1") (pintype "passive"))
      (node (ref "R7") (pin "1") (pinfunction "1_1") (pintype "passive"))
    )
    (net (code "21") (name "Net-(D2-Pad1)") (class "Default")
      (node (ref "D2") (pin "1") (pinfunction "1_1") (pintype "passive"))
      (node (ref "R15") (pin "1") (pinfunction "1_1") (pintype "passive"))
    )
    (net (code "22") (name "Net-(D3-Pad1)") (class "Default")
      (node (ref "D3") (pin "1") (pinfunction "1_1") (pintype "passive"))
      (node (ref "R23") (pin "2") (pinfunction "2_2") (pintype "passive"))
    )
    (net (code "23") (name "Net-(IC2-IN+)") (class "Default")
      (node (ref "C5") (pin "1") (pinfunction "1_1") (pintype "passive"))
      (node (ref "IC2") (pin "2") (pinfunction "IN+_2") (pintype "passive"))
      (node (ref "R3") (pin "1") (pinfunction "1_1") (pintype "passive"))
    )
    (net (code "24") (name "Net-(IC2-IN-)") (class "Default")
      (node (ref "C5") (pin "2") (pinfunction "2_2") (pintype "passive"))
      (node (ref "IC2") (pin "3") (pinfunction "IN-_3") (pintype "passive"))
      (node (ref "R6") (pin "1") (pinfunction "1_1") (pintype "passive"))
    )
    (net (code "25") (name "Net-(IC2-NC)") (class "Default")
      (node (ref "IC2") (pin "1") (pinfunction "NC_1") (pintype "passive"))
      (node (ref "R2") (pin "1") (pinfunction "1_1") (pintype "passive"))
    )
    (net (code "26") (name "Net-(IC2-OUT)") (class "Default")
      (node (ref "IC2") (pin "8") (pinfunction "OUT_8") (pintype "passive"))
      (node (ref "R1") (pin "2") (pinfunction "2_2") (pintype "passive"))
    )
    (net (code "27") (name "Net-(IC2-REF1)") (class "Default")
      (node (ref "C6") (pin "2") (pinfunction "2_2") (pintype "passive"))
      (node (ref "IC2") (pin "6") (pinfunction "REF2_6") (pintype "passive"))
      (node (ref "IC2") (pin "7") (pinfunction "REF1_7") (pintype "passive"))
      (node (ref "R4") (pin "2") (pinfunction "2_2") (pintype "passive"))
      (node (ref "R5") (pin "2") (pinfunction "2_2") (pintype "passive"))
    )
    (net (code "28") (name "Net-(IC3-IP+)") (class "Default")
      (node (ref "IC3") (pin "4") (pinfunction "IP+_4") (pintype "passive"))
      (node (ref "L1") (pin "2") (pinfunction "2_2") (pintype "passive"))
      (node (ref "R8") (pin "I1") (pinfunction "I1_I1") (pintype "passive"))
    )
    (net (code "29") (name "Net-(IC6-DT)") (class "Default")
      (node (ref "C38") (pin "2") (pinfunction "2_2") (pintype "passive"))
      (node (ref "IC6") (pin "6") (pinfunction "DT_6") (pintype "passive"))
      (node (ref "R42") (pin "2") (pinfunction "2_2") (pintype "passive"))
    )
    (net (code "30") (name "Net-(IC6-INA)") (class "Default")
      (node (ref "C34") (pin "1") (pinfunction "1_1") (pintype "passive"))
      (node (ref "D5") (pin "1") (pinfunction "1_1") (pintype "passive"))
      (node (ref "IC6") (pin "1") (pinfunction "INA_1") (pintype "passive"))
      (node (ref "R28") (pin "2") (pinfunction "2_2") (pintype "passive"))
      (node (ref "R33") (pin "2") (pinfunction "2_2") (pintype "passive"))
      (node (ref "TP9") (pin "1") (pinfunction "B_1") (pintype "passive"))
    )
    (net (code "31") (name "Net-(IC6-INB)") (class "Default")
      (node (ref "C33") (pin "1") (pinfunction "1_1") (pintype "passive"))
      (node (ref "D4") (pin "1") (pinfunction "1_1") (pintype "passive"))
      (node (ref "IC6") (pin "2") (pinfunction "INB_2") (pintype "passive"))
      (node (ref "R29") (pin "2") (pinfunction "2_2") (pintype "passive"))
      (node (ref "R32") (pin "2") (pinfunction "2_2") (pintype "passive"))
      (node (ref "TP11") (pin "1") (pinfunction "B_1") (pintype "passive"))
    )
    (net (code "32") (name "Net-(LED1-Pad1)") (class "Default")
      (node (ref "LED1") (pin "1") (pinfunction "1_1") (pintype "passive"))
      (node (ref "R11") (pin "2") (pinfunction "2_2") (pintype "passive"))
    )
    (net (code "33") (name "Net-(LED2-Pad1)") (class "Default")
      (node (ref "LED2") (pin "1") (pinfunction "1_1") (pintype "passive"))
      (node (ref "R14") (pin "2") (pinfunction "2_2") (pintype "passive"))
    )
    (net (code "34") (name "P_GND") (class "Default")
      (node (ref "C1") (pin "1") (pinfunction "1_1") (pintype "passive"))
      (node (ref "C10") (pin "1") (pinfunction "1_1") (pintype "passive"))
      (node (ref "C11") (pin "2") (pinfunction "-_2") (pintype "passive"))
      (node (ref "C12") (pin "2") (pinfunction "-_2") (pintype "passive"))
      (node (ref "C13") (pin "2") (pinfunction "-_2") (pintype "passive"))
      (node (ref "C15") (pin "1") (pinfunction "1_1") (pintype "passive"))
      (node (ref "C16") (pin "1") (pinfunction "1_1") (pintype "passive"))
      (node (ref "C17") (pin "1") (pinfunction "1_1") (pintype "passive"))
      (node (ref "C18") (pin "2") (pinfunction "-_2") (pintype "passive"))
      (node (ref "C19") (pin "2") (pinfunction "-_2") (pintype "passive"))
      (node (ref "C2") (pin "1") (pinfunction "1_1") (pintype "passive"))
      (node (ref "C20") (pin "2") (pinfunction "-_2") (pintype "passive"))
      (node (ref "C21") (pin "1") (pinfunction "1_1") (pintype "passive"))
      (node (ref "C22") (pin "1") (pinfunction "1_1") (pintype "passive"))
      (node (ref "C23") (pin "1") (pinfunction "1_1") (pintype "passive"))
      (node (ref "C24") (pin "1") (pinfunction "1_1") (pintype "passive"))
      (node (ref "C25") (pin "1") (pinfunction "1_1") (pintype "passive"))
      (node (ref "C26") (pin "1") (pinfunction "1_1") (pintype "passive"))
      (node (ref "C27") (pin "1") (pinfunction "1_1") (pintype "passive"))
      (node (ref "C28") (pin "1") (pinfunction "1_1") (pintype "passive"))
      (node (ref "C3") (pin "1") (pinfunction "1_1") (pintype "passive"))
      (node (ref "C31") (pin "1") (pinfunction "1_1") (pintype "passive"))
      (node (ref "C33") (pin "2") (pinfunction "2_2") (pintype "passive"))
      (node (ref "C34") (pin "2") (pinfunction "2_2") (pintype "passive"))
      (node (ref "C35") (pin "2") (pinfunction "2_2") (pintype "passive"))
      (node (ref "C37") (pin "1") (pinfunction "1_1") (pintype "passive"))
      (node (ref "C38") (pin "1") (pinfunction "1_1") (pintype "passive"))
      (node (ref "C4") (pin "1") (pinfunction "1_1") (pintype "passive"))
      (node (ref "C6") (pin "1") (pinfunction "1_1") (pintype "passive"))
      (node (ref "C7") (pin "2") (pinfunction "2_2") (pintype "passive"))
      (node (ref "C8") (pin "1") (pinfunction "1_1") (pintype "passive"))
      (node (ref "C9") (pin "1") (pinfunction "1_1") (pintype "passive"))
      (node (ref "IC1") (pin "2") (pinfunction "GND_2") (pintype "passive"))
      (node (ref "IC2") (pin "4") (pinfunction "GND_4") (pintype "passive"))
      (node (ref "IC3") (pin "2") (pinfunction "GND_2") (pintype "passive"))
      (node (ref "IC4") (pin "2") (pinfunction "GND_2") (pintype "passive"))
      (node (ref "IC6") (pin "4") (pinfunction "GND_4") (pintype "passive"))
      (node (ref "IC6") (pin "9") (pinfunction "VSSB_9") (pintype "passive"))
      (node (ref "J2") (pin "1") (pinfunction "1_1") (pintype "passive"))
      (node (ref "J4") (pin "1") (pinfunction "1_1") (pintype "passive"))
      (node (ref "LED1") (pin "2") (pinfunction "2_2") (pintype "passive"))
      (node (ref "LED2") (pin "2") (pinfunction "2_2") (pintype "passive"))
      (node (ref "Q2") (pin "2") (pinfunction "S_1_2") (pintype "passive"))
      (node (ref "Q2") (pin "3") (pinfunction "S_2_3") (pintype "passive"))
      (node (ref "Q2") (pin "4") (pinfunction "S_3_4") (pintype "passive"))
      (node (ref "Q2") (pin "5") (pinfunction "S_4_5") (pintype "passive"))
      (node (ref "Q2") (pin "6") (pinfunction "S_5_6") (pintype "passive"))
      (node (ref "Q2") (pin "7") (pinfunction "S_6_7") (pintype "passive"))
      (node (ref "Q2") (pin "8") (pinfunction "S_7_8") (pintype "passive"))
      (node (ref "Q2") (pin "A2") (pinfunction "S_8_A2") (pintype "passive"))
      (node (ref "R12") (pin "1") (pinfunction "1_1") (pintype "passive"))
      (node (ref "R16") (pin "1") (pinfunction "1_1") (pintype "passive"))
      (node (ref "R18") (pin "1") (pinfunction "1_1") (pintype "passive"))
      (node (ref "R2") (pin "2") (pinfunction "2_2") (pintype "passive"))
      (node (ref "R32") (pin "1") (pinfunction "1_1") (pintype "passive"))
      (node (ref "R33") (pin "1") (pinfunction "1_1") (pintype "passive"))
      (node (ref "R39") (pin "1") (pinfunction "1_1") (pintype "passive"))
      (node (ref "R42") (pin "1") (pinfunction "1_1") (pintype "passive"))
      (node (ref "R5") (pin "1") (pinfunction "1_1") (pintype "passive"))
      (node (ref "R9") (pin "1") (pinfunction "1_1") (pintype "passive"))
      (node (ref "R9") (pin "2") (pinfunction "2_2") (pintype "passive"))
      (node (ref "TP10") (pin "1") (pinfunction "B_1") (pintype "passive"))
      (node (ref "TP12") (pin "1") (pinfunction "B_1") (pintype "passive"))
      (node (ref "TP6") (pin "1") (pinfunction "TP_1") (pintype "passive"))
      (node (ref "TP7") (pin "1") (pinfunction "B_1") (pintype "passive"))
      (node (ref "TP8") (pin "1") (pinfunction "B_1") (pintype "passive"))
    )
    (net (code "35") (name "VDD_5P0") (class "Default")
      (node (ref "C23") (pin "2") (pinfunction "2_2") (pintype "passive"))
      (node (ref "C24") (pin "2") (pinfunction "2_2") (pintype "passive"))
      (node (ref "C31") (pin "2") (pinfunction "2_2") (pintype "passive"))
      (node (ref "C7") (pin "1") (pinfunction "1_1") (pintype "passive"))
      (node (ref "C8") (pin "2") (pinfunction "2_2") (pintype "passive"))
      (node (ref "D4") (pin "2") (pinfunction "2_2") (pintype "passive"))
      (node (ref "D5") (pin "2") (pinfunction "2_2") (pintype "passive"))
      (node (ref "IC1") (pin "1") (pinfunction "VCC_1") (pintype "passive"))
      (node (ref "IC2") (pin "5") (pinfunction "VS_5") (pintype "passive"))
      (node (ref "IC3") (pin "1") (pinfunction "VCC_1") (pintype "passive"))
      (node (ref "IC4") (pin "1") (pinfunction "VCC_1") (pintype "passive"))
      (node (ref "IC6") (pin "3") (pinfunction "VCCI_1_3") (pintype "passive"))
      (node (ref "IC6") (pin "8") (pinfunction "VCCI_2_8") (pintype "passive"))
      (node (ref "R4") (pin "1") (pinfunction "1_1") (pintype "passive"))
    )
    (net (code "36") (name "VDD_12P0") (class "Default")
      (node (ref "C35") (pin "1") (pinfunction "1_1") (pintype "passive"))
      (node (ref "IC6") (pin "11") (pinfunction "VDDB_11") (pintype "passive"))
      (node (ref "R23") (pin "1") (pinfunction "1_1") (pintype "passive"))
    )
    (net (code "37") (name "unconnected-(IC6-NC_1-Pad7)") (class "Default")
      (node (ref "IC6") (pin "7") (pinfunction "NC_1_7") (pintype "passive+no_connect"))
    )
    (net (code "38") (name "unconnected-(IC6-NC_2-Pad12)") (class "Default")
      (node (ref "IC6") (pin "12") (pinfunction "NC_2_12") (pintype "passive+no_connect"))
    )
    (net (code "39") (name "unconnected-(IC6-NC_3-Pad13)") (class "Default")
      (node (ref "IC6") (pin "13") (pinfunction "NC_3_13") (pintype "passive+no_connect"))
    )
  )
)
